# a26-flashcart-v2.net
KiCad netlist of a schematic drawn in EAGLE
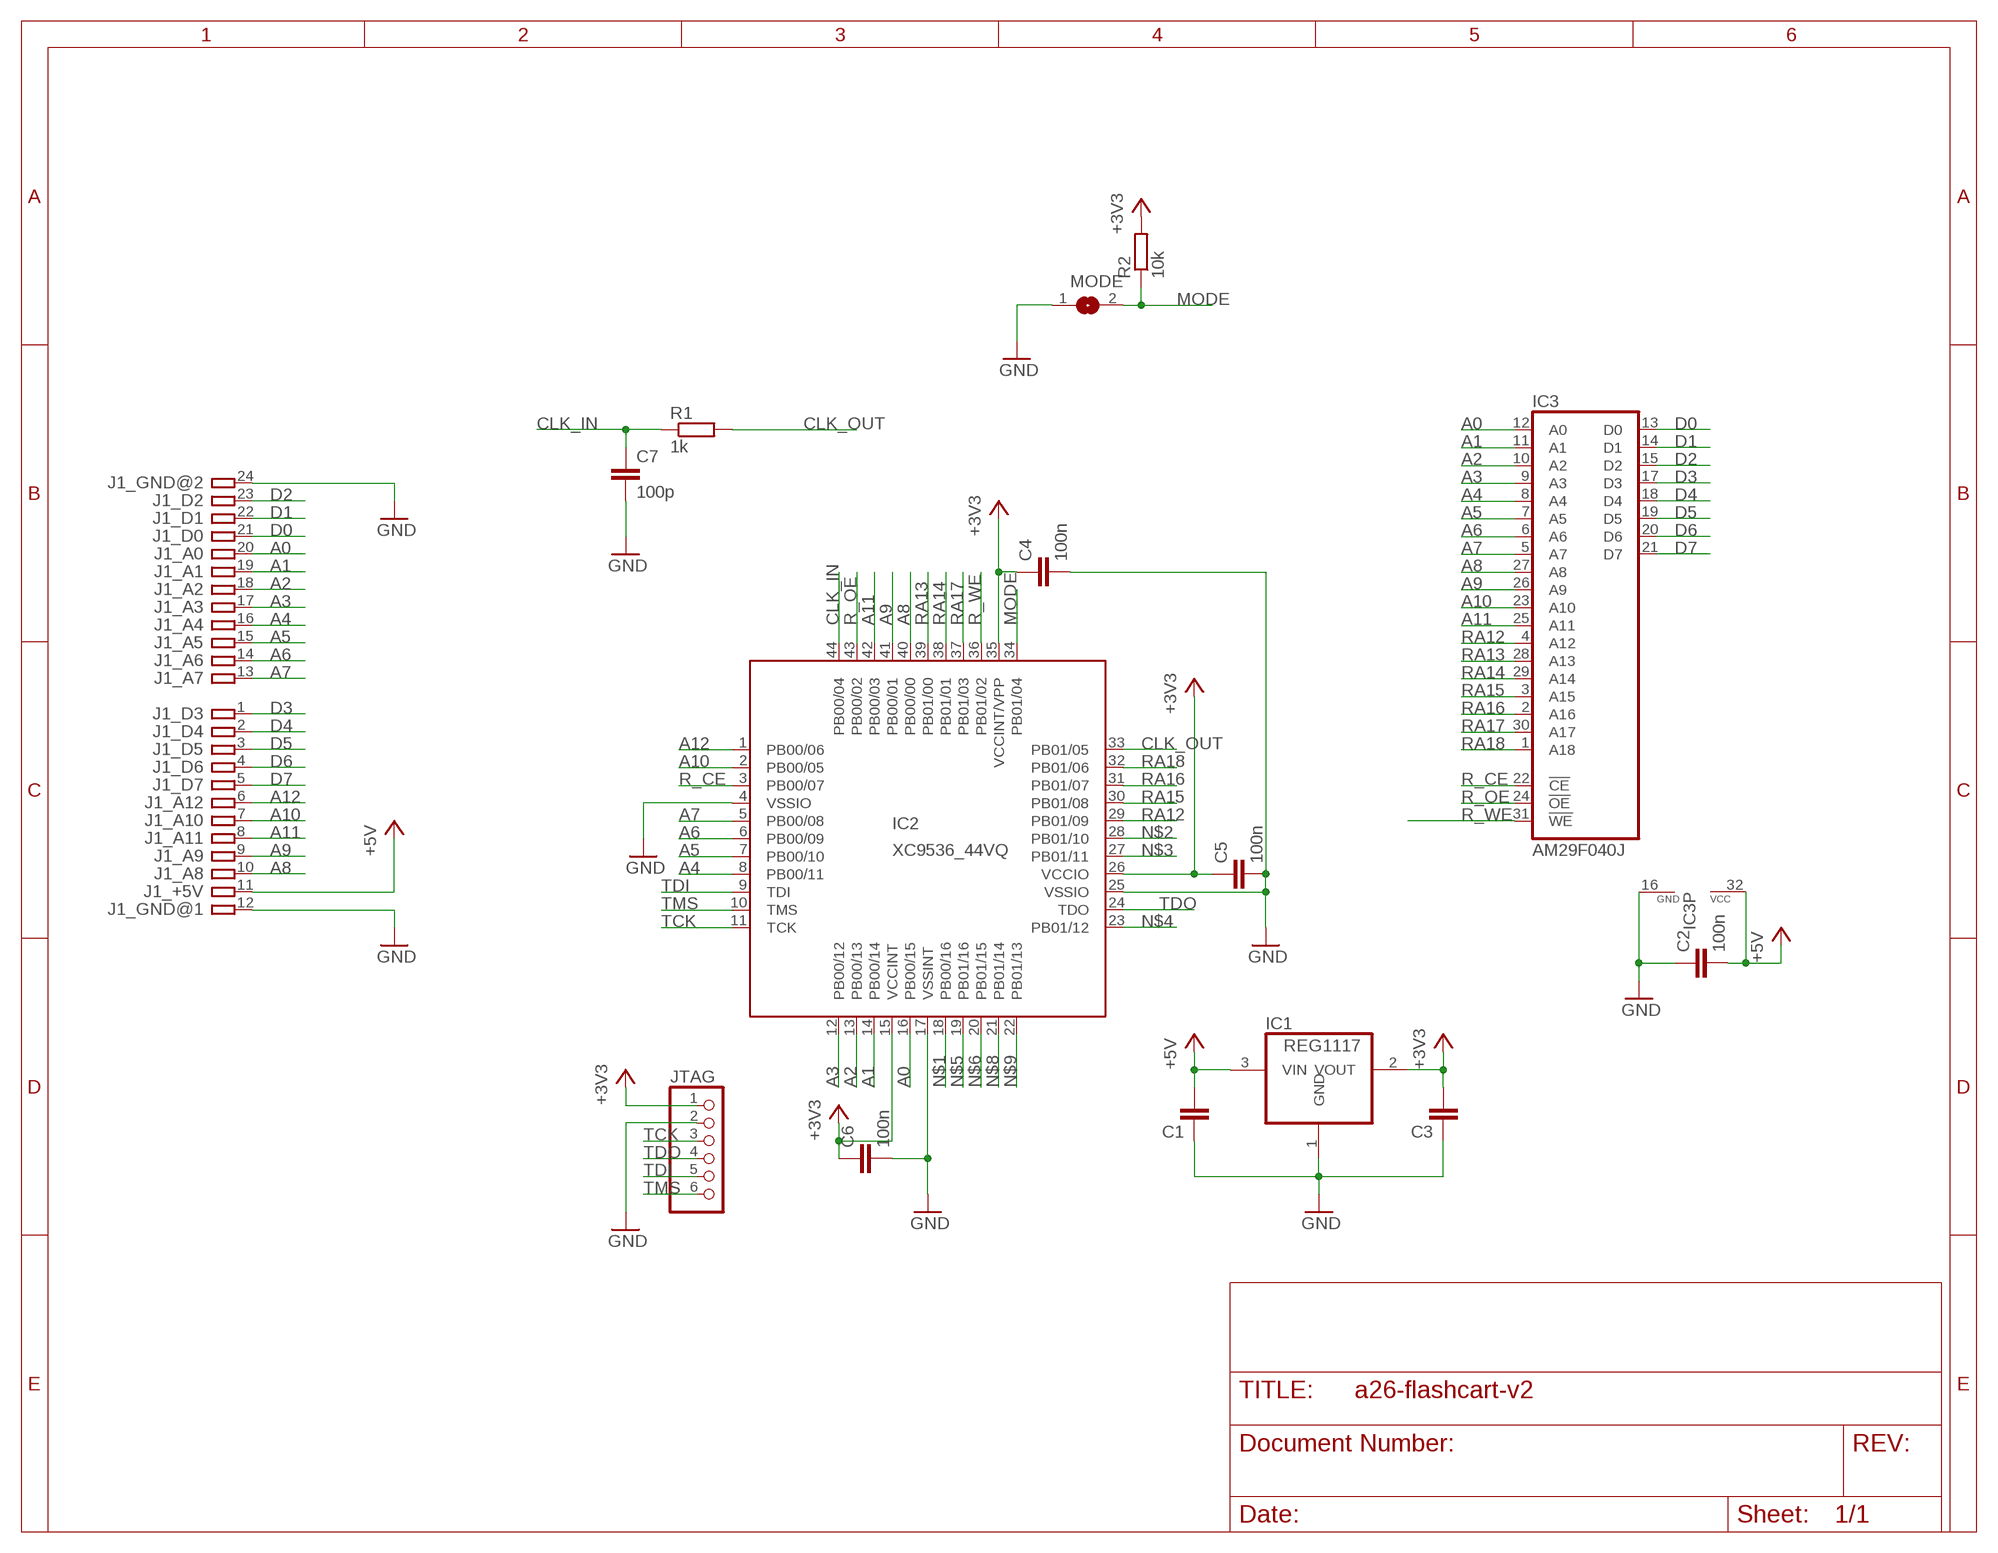
[diagram p0: schematic, sheet 1]

(export (version "E")
  (design (tool "Eeschema 10.0.6"))
  (components
    (comp (ref "C1")
      (value "C-EUC0805")
      (footprint "eagle-import:C0805")
      (libsource (lib "eagle-import") (part "C-EUC0805"))
    )
    (comp (ref "C2")
      (value "100n")
      (footprint "eagle-import:C0805")
      (libsource (lib "eagle-import") (part "C-EUC0805"))
    )
    (comp (ref "C3")
      (value "C-EUC0805")
      (footprint "eagle-import:C0805")
      (libsource (lib "eagle-import") (part "C-EUC0805"))
    )
    (comp (ref "C4")
      (value "100n")
      (footprint "eagle-import:C0805")
      (libsource (lib "eagle-import") (part "C-EUC0805"))
    )
    (comp (ref "C5")
      (value "100n")
      (footprint "eagle-import:C0805")
      (libsource (lib "eagle-import") (part "C-EUC0805"))
    )
    (comp (ref "C6")
      (value "100n")
      (footprint "eagle-import:C0805")
      (libsource (lib "eagle-import") (part "C-EUC0805"))
    )
    (comp (ref "C7")
      (value "100p")
      (footprint "eagle-import:C0805")
      (libsource (lib "eagle-import") (part "C-EUC0805"))
    )
    (comp (ref "IC1")
      (value "REG1117")
      (footprint "eagle-import:SOT223")
      (libsource (lib "eagle-import") (part "REG1117"))
    )
    (comp (ref "IC2")
      (value "XC9536_44VQ")
      (footprint "eagle-import:SQFP-S-10X10-44")
      (fields (field (name "MPN") "XC9536-15VQG44C"))
      (libsource (lib "eagle-import") (part "XC9536_44VQ"))
    )
    (comp (ref "IC3")
      (value "AM29F040J")
      (footprint "eagle-import:PLCC32R")
      (libsource (lib "eagle-import") (part "AM29F040J"))
    )
    (comp (ref "J1")
      (value "ATARI-2600-SMALL")
      (footprint "eagle-import:ATARI-2600-SMALL")
      (libsource (lib "eagle-import") (part "ATARI-2600-SMALL"))
    )
    (comp (ref "JTAG")
      (value "PINHD-1X6")
      (footprint "eagle-import:1X06")
      (libsource (lib "eagle-import") (part "PINHD-1X6"))
    )
    (comp (ref "MODE")
      (value "SJ")
      (footprint "eagle-import:SJ")
      (libsource (lib "eagle-import") (part "SJ"))
    )
    (comp (ref "R1")
      (value "1k")
      (footprint "eagle-import:R0805")
      (libsource (lib "eagle-import") (part "R-EU_R0805"))
    )
    (comp (ref "R2")
      (value "10k")
      (footprint "eagle-import:R0805")
      (libsource (lib "eagle-import") (part "R-EU_R0805"))
    )
  )
  (nets
    (net (code "1") (name "+3V3") (class "Default")
      (node (ref "C3") (pin "2") (pinfunction "2_2") (pintype "passive"))
      (node (ref "C4") (pin "1") (pinfunction "1_1") (pintype "passive"))
      (node (ref "C5") (pin "1") (pinfunction "1_1") (pintype "passive"))
      (node (ref "C6") (pin "1") (pinfunction "1_1") (pintype "passive"))
      (node (ref "IC1") (pin "2") (pinfunction "VOUT_2") (pintype "output"))
      (node (ref "IC2") (pin "15") (pinfunction "VCCINT_15") (pintype "power_in"))
      (node (ref "IC2") (pin "26") (pinfunction "VCCIO_26") (pintype "power_in"))
      (node (ref "IC2") (pin "35") (pinfunction "VCCINT/VPP_35") (pintype "input"))
      (node (ref "JTAG") (pin "1") (pinfunction "1_1") (pintype "passive"))
      (node (ref "R2") (pin "2") (pinfunction "2_2") (pintype "passive"))
    )
    (net (code "2") (name "+5V") (class "Default")
      (node (ref "C1") (pin "2") (pinfunction "2_2") (pintype "passive"))
      (node (ref "C2") (pin "2") (pinfunction "2_2") (pintype "passive"))
      (node (ref "IC1") (pin "3") (pinfunction "VIN_3") (pintype "input"))
      (node (ref "IC3") (pin "32") (pinfunction "VCC_32") (pintype "power_in"))
      (node (ref "J1") (pin "11") (pinfunction "P_11") (pintype "bidirectional"))
    )
    (net (code "3") (name "/A0") (class "Default")
      (node (ref "IC2") (pin "16") (pinfunction "PB00/15_16") (pintype "bidirectional"))
      (node (ref "IC3") (pin "12") (pinfunction "A0_12") (pintype "input"))
      (node (ref "J1") (pin "20") (pinfunction "P_20") (pintype "bidirectional"))
    )
    (net (code "4") (name "/A1") (class "Default")
      (node (ref "IC2") (pin "14") (pinfunction "PB00/14_14") (pintype "bidirectional"))
      (node (ref "IC3") (pin "11") (pinfunction "A1_11") (pintype "input"))
      (node (ref "J1") (pin "19") (pinfunction "P_19") (pintype "bidirectional"))
    )
    (net (code "5") (name "/A2") (class "Default")
      (node (ref "IC2") (pin "13") (pinfunction "PB00/13_13") (pintype "bidirectional"))
      (node (ref "IC3") (pin "10") (pinfunction "A2_10") (pintype "input"))
      (node (ref "J1") (pin "18") (pinfunction "P_18") (pintype "bidirectional"))
    )
    (net (code "6") (name "/A3") (class "Default")
      (node (ref "IC2") (pin "12") (pinfunction "PB00/12_12") (pintype "bidirectional"))
      (node (ref "IC3") (pin "9") (pinfunction "A3_9") (pintype "input"))
      (node (ref "J1") (pin "17") (pinfunction "P_17") (pintype "bidirectional"))
    )
    (net (code "7") (name "/A4") (class "Default")
      (node (ref "IC2") (pin "8") (pinfunction "PB00/11_8") (pintype "bidirectional"))
      (node (ref "IC3") (pin "8") (pinfunction "A4_8") (pintype "input"))
      (node (ref "J1") (pin "16") (pinfunction "P_16") (pintype "bidirectional"))
    )
    (net (code "8") (name "/A5") (class "Default")
      (node (ref "IC2") (pin "7") (pinfunction "PB00/10_7") (pintype "bidirectional"))
      (node (ref "IC3") (pin "7") (pinfunction "A5_7") (pintype "input"))
      (node (ref "J1") (pin "15") (pinfunction "P_15") (pintype "bidirectional"))
    )
    (net (code "9") (name "/A6") (class "Default")
      (node (ref "IC2") (pin "6") (pinfunction "PB00/09_6") (pintype "bidirectional"))
      (node (ref "IC3") (pin "6") (pinfunction "A6_6") (pintype "input"))
      (node (ref "J1") (pin "14") (pinfunction "P_14") (pintype "bidirectional"))
    )
    (net (code "10") (name "/A7") (class "Default")
      (node (ref "IC2") (pin "5") (pinfunction "PB00/08_5") (pintype "bidirectional"))
      (node (ref "IC3") (pin "5") (pinfunction "A7_5") (pintype "input"))
      (node (ref "J1") (pin "13") (pinfunction "P_13") (pintype "bidirectional"))
    )
    (net (code "11") (name "/A8") (class "Default")
      (node (ref "IC2") (pin "40") (pinfunction "PB00/00_40") (pintype "bidirectional"))
      (node (ref "IC3") (pin "27") (pinfunction "A8_27") (pintype "input"))
      (node (ref "J1") (pin "10") (pinfunction "P_10") (pintype "bidirectional"))
    )
    (net (code "12") (name "/A9") (class "Default")
      (node (ref "IC2") (pin "41") (pinfunction "PB00/01_41") (pintype "bidirectional"))
      (node (ref "IC3") (pin "26") (pinfunction "A9_26") (pintype "input"))
      (node (ref "J1") (pin "9") (pinfunction "P_9") (pintype "bidirectional"))
    )
    (net (code "13") (name "/A10") (class "Default")
      (node (ref "IC2") (pin "2") (pinfunction "PB00/05_2") (pintype "bidirectional"))
      (node (ref "IC3") (pin "23") (pinfunction "A10_23") (pintype "input"))
      (node (ref "J1") (pin "7") (pinfunction "P_7") (pintype "bidirectional"))
    )
    (net (code "14") (name "/A11") (class "Default")
      (node (ref "IC2") (pin "42") (pinfunction "PB00/03_42") (pintype "bidirectional"))
      (node (ref "IC3") (pin "25") (pinfunction "A11_25") (pintype "input"))
      (node (ref "J1") (pin "8") (pinfunction "P_8") (pintype "bidirectional"))
    )
    (net (code "15") (name "/A12") (class "Default")
      (node (ref "IC2") (pin "1") (pinfunction "PB00/06_1") (pintype "bidirectional"))
      (node (ref "J1") (pin "6") (pinfunction "P_6") (pintype "bidirectional"))
    )
    (net (code "16") (name "/CLK_IN") (class "Default")
      (node (ref "C7") (pin "1") (pinfunction "1_1") (pintype "passive"))
      (node (ref "IC2") (pin "44") (pinfunction "PB00/04_44") (pintype "bidirectional"))
      (node (ref "R1") (pin "1") (pinfunction "1_1") (pintype "passive"))
    )
    (net (code "17") (name "/CLK_OUT") (class "Default")
      (node (ref "IC2") (pin "33") (pinfunction "PB01/05_33") (pintype "bidirectional"))
      (node (ref "R1") (pin "2") (pinfunction "2_2") (pintype "passive"))
    )
    (net (code "18") (name "/D0") (class "Default")
      (node (ref "IC3") (pin "13") (pinfunction "D0_13") (pintype "tri_state"))
      (node (ref "J1") (pin "21") (pinfunction "P_21") (pintype "bidirectional"))
    )
    (net (code "19") (name "/D1") (class "Default")
      (node (ref "IC3") (pin "14") (pinfunction "D1_14") (pintype "tri_state"))
      (node (ref "J1") (pin "22") (pinfunction "P_22") (pintype "bidirectional"))
    )
    (net (code "20") (name "/D2") (class "Default")
      (node (ref "IC3") (pin "15") (pinfunction "D2_15") (pintype "tri_state"))
      (node (ref "J1") (pin "23") (pinfunction "P_23") (pintype "bidirectional"))
    )
    (net (code "21") (name "/D3") (class "Default")
      (node (ref "IC3") (pin "17") (pinfunction "D3_17") (pintype "tri_state"))
      (node (ref "J1") (pin "1") (pinfunction "P_1") (pintype "bidirectional"))
    )
    (net (code "22") (name "/D4") (class "Default")
      (node (ref "IC3") (pin "18") (pinfunction "D4_18") (pintype "tri_state"))
      (node (ref "J1") (pin "2") (pinfunction "P_2") (pintype "bidirectional"))
    )
    (net (code "23") (name "/D5") (class "Default")
      (node (ref "IC3") (pin "19") (pinfunction "D5_19") (pintype "tri_state"))
      (node (ref "J1") (pin "3") (pinfunction "P_3") (pintype "bidirectional"))
    )
    (net (code "24") (name "/D6") (class "Default")
      (node (ref "IC3") (pin "20") (pinfunction "D6_20") (pintype "tri_state"))
      (node (ref "J1") (pin "4") (pinfunction "P_4") (pintype "bidirectional"))
    )
    (net (code "25") (name "/D7") (class "Default")
      (node (ref "IC3") (pin "21") (pinfunction "D7_21") (pintype "tri_state"))
      (node (ref "J1") (pin "5") (pinfunction "P_5") (pintype "bidirectional"))
    )
    (net (code "26") (name "/MODE") (class "Default")
      (node (ref "IC2") (pin "34") (pinfunction "PB01/04_34") (pintype "bidirectional"))
      (node (ref "MODE") (pin "2") (pinfunction "2_2") (pintype "passive"))
      (node (ref "R2") (pin "1") (pinfunction "1_1") (pintype "passive"))
    )
    (net (code "27") (name "/N$1") (class "Default")
      (node (ref "IC2") (pin "18") (pinfunction "PB00/16_18") (pintype "bidirectional"))
    )
    (net (code "28") (name "/N$2") (class "Default")
      (node (ref "IC2") (pin "28") (pinfunction "PB01/10_28") (pintype "bidirectional"))
    )
    (net (code "29") (name "/N$3") (class "Default")
      (node (ref "IC2") (pin "27") (pinfunction "PB01/11_27") (pintype "bidirectional"))
    )
    (net (code "30") (name "/N$4") (class "Default")
      (node (ref "IC2") (pin "23") (pinfunction "PB01/12_23") (pintype "bidirectional"))
    )
    (net (code "31") (name "/N$5") (class "Default")
      (node (ref "IC2") (pin "19") (pinfunction "PB01/16_19") (pintype "bidirectional"))
    )
    (net (code "32") (name "/N$6") (class "Default")
      (node (ref "IC2") (pin "20") (pinfunction "PB01/15_20") (pintype "bidirectional"))
    )
    (net (code "33") (name "/N$8") (class "Default")
      (node (ref "IC2") (pin "21") (pinfunction "PB01/14_21") (pintype "bidirectional"))
    )
    (net (code "34") (name "/N$9") (class "Default")
      (node (ref "IC2") (pin "22") (pinfunction "PB01/13_22") (pintype "bidirectional"))
    )
    (net (code "35") (name "/RA12") (class "Default")
      (node (ref "IC2") (pin "29") (pinfunction "PB01/09_29") (pintype "bidirectional"))
      (node (ref "IC3") (pin "4") (pinfunction "A12_4") (pintype "input"))
    )
    (net (code "36") (name "/RA13") (class "Default")
      (node (ref "IC2") (pin "39") (pinfunction "PB01/00_39") (pintype "bidirectional"))
      (node (ref "IC3") (pin "28") (pinfunction "A13_28") (pintype "input"))
    )
    (net (code "37") (name "/RA14") (class "Default")
      (node (ref "IC2") (pin "38") (pinfunction "PB01/01_38") (pintype "bidirectional"))
      (node (ref "IC3") (pin "29") (pinfunction "A14_29") (pintype "input"))
    )
    (net (code "38") (name "/RA15") (class "Default")
      (node (ref "IC2") (pin "30") (pinfunction "PB01/08_30") (pintype "bidirectional"))
      (node (ref "IC3") (pin "3") (pinfunction "A15_3") (pintype "input"))
    )
    (net (code "39") (name "/RA16") (class "Default")
      (node (ref "IC2") (pin "31") (pinfunction "PB01/07_31") (pintype "bidirectional"))
      (node (ref "IC3") (pin "2") (pinfunction "A16_2") (pintype "input"))
    )
    (net (code "40") (name "/RA17") (class "Default")
      (node (ref "IC2") (pin "37") (pinfunction "PB01/03_37") (pintype "bidirectional"))
      (node (ref "IC3") (pin "30") (pinfunction "A17_30") (pintype "input"))
    )
    (net (code "41") (name "/RA18") (class "Default")
      (node (ref "IC2") (pin "32") (pinfunction "PB01/06_32") (pintype "bidirectional"))
      (node (ref "IC3") (pin "1") (pinfunction "A18_1") (pintype "input"))
    )
    (net (code "42") (name "/R_CE") (class "Default")
      (node (ref "IC2") (pin "3") (pinfunction "PB00/07_3") (pintype "bidirectional"))
      (node (ref "IC3") (pin "22") (pinfunction "~{CE}_22") (pintype "input"))
    )
    (net (code "43") (name "/R_OE") (class "Default")
      (node (ref "IC2") (pin "43") (pinfunction "PB00/02_43") (pintype "bidirectional"))
      (node (ref "IC3") (pin "24") (pinfunction "~{OE}_24") (pintype "input"))
    )
    (net (code "44") (name "/R_WE") (class "Default")
      (node (ref "IC2") (pin "36") (pinfunction "PB01/02_36") (pintype "bidirectional"))
      (node (ref "IC3") (pin "31") (pinfunction "~{WE}_31") (pintype "input"))
    )
    (net (code "45") (name "/TCK") (class "Default")
      (node (ref "IC2") (pin "11") (pinfunction "TCK_11") (pintype "input"))
      (node (ref "JTAG") (pin "3") (pinfunction "3_3") (pintype "passive"))
    )
    (net (code "46") (name "/TDI") (class "Default")
      (node (ref "IC2") (pin "9") (pinfunction "TDI_9") (pintype "input"))
      (node (ref "JTAG") (pin "5") (pinfunction "5_5") (pintype "passive"))
    )
    (net (code "47") (name "/TDO") (class "Default")
      (node (ref "IC2") (pin "24") (pinfunction "TDO_24") (pintype "output"))
      (node (ref "JTAG") (pin "4") (pinfunction "4_4") (pintype "passive"))
    )
    (net (code "48") (name "/TMS") (class "Default")
      (node (ref "IC2") (pin "10") (pinfunction "TMS_10") (pintype "input"))
      (node (ref "JTAG") (pin "6") (pinfunction "6_6") (pintype "passive"))
    )
    (net (code "49") (name "GND") (class "Default")
      (node (ref "C1") (pin "1") (pinfunction "1_1") (pintype "passive"))
      (node (ref "C2") (pin "1") (pinfunction "1_1") (pintype "passive"))
      (node (ref "C3") (pin "1") (pinfunction "1_1") (pintype "passive"))
      (node (ref "C4") (pin "2") (pinfunction "2_2") (pintype "passive"))
      (node (ref "C5") (pin "2") (pinfunction "2_2") (pintype "passive"))
      (node (ref "C6") (pin "2") (pinfunction "2_2") (pintype "passive"))
      (node (ref "C7") (pin "2") (pinfunction "2_2") (pintype "passive"))
      (node (ref "IC1") (pin "1") (pinfunction "GND_1") (pintype "power_in"))
      (node (ref "IC2") (pin "17") (pinfunction "VSSINT_17") (pintype "power_in"))
      (node (ref "IC2") (pin "25") (pinfunction "VSSIO_25") (pintype "power_in"))
      (node (ref "IC2") (pin "4") (pinfunction "VSSIO_4") (pintype "power_in"))
      (node (ref "IC3") (pin "16") (pinfunction "GND_16") (pintype "power_in"))
      (node (ref "J1") (pin "12") (pinfunction "P_12") (pintype "bidirectional"))
      (node (ref "J1") (pin "24") (pinfunction "P_24") (pintype "bidirectional"))
      (node (ref "JTAG") (pin "2") (pinfunction "2_2") (pintype "passive"))
      (node (ref "MODE") (pin "1") (pinfunction "1_1") (pintype "passive"))
    )
  )
)
